# PROC091F_PMIC.net
KiCad netlist of a schematic drawn in Altium Designer
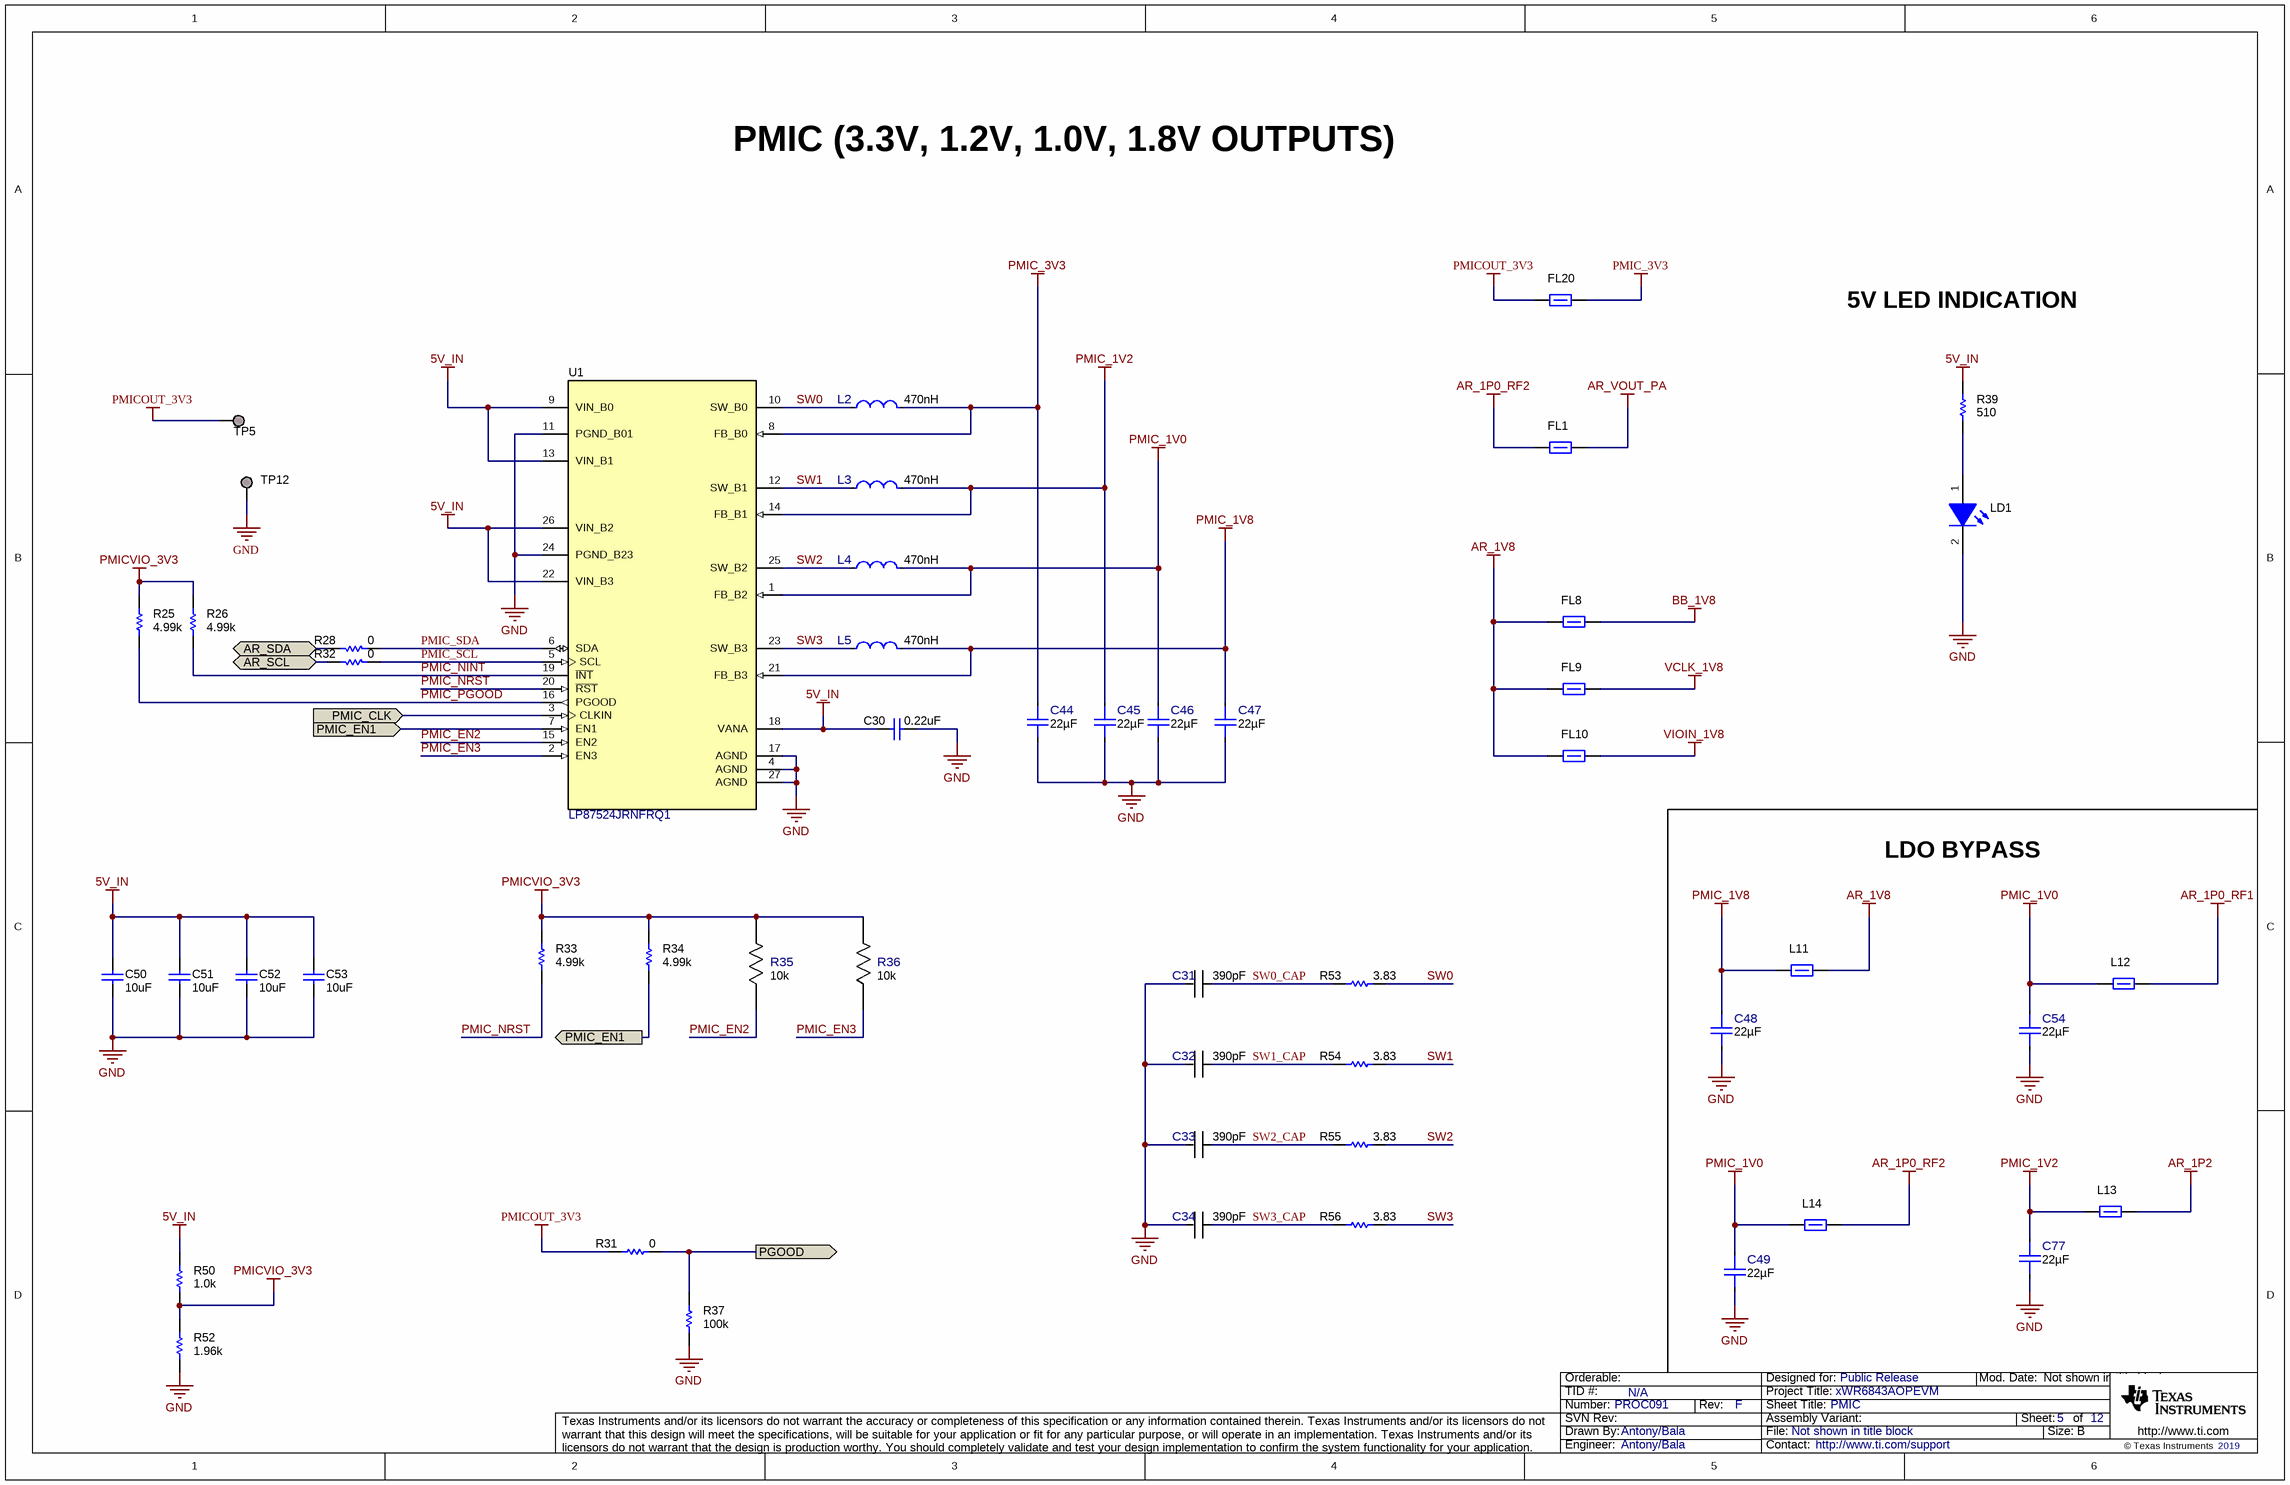
[diagram p0: PROC091F_PMIC.SchDoc]

(export (version "E")
  (design (tool "Eeschema 10.0.6"))
  (components
    (comp (ref "C30")
      (value "0.22uF")
      (footprint "0201_033L")
      (description "CAP, CERM, 0.22 uF, 10 V, +/- 20%, X5R, 0201")
      (fields
        (field (name "MANUFACTURER") "Taiyo Yuden")
        (field (name "PARTNUMBER") "LMK063BJ224MP-F")
        (field (name "PUBLISHER") "Texas Instruments")
      )
      (libsource (lib "Altium Vault - TI") (part "Capacitor"))
    )
    (comp (ref "C31")
      (value "TMK063CG391JT-F")
      (footprint "FP-TMK063CG391JT-F_0201 (0603 Metric)-IPC_C")
      (description "CAP CER 390PF 25V C0G/NP0 0201")
      (fields (field (name "CAP_F") "390pF") (field (name "MANUFACTURER") "Taiyo Yuden"))
      (libsource (lib "Altium Vault - TI") (part "SYM-B32642B0223J"))
    )
    (comp (ref "C32")
      (value "TMK063CG391JT-F")
      (footprint "FP-TMK063CG391JT-F_0201 (0603 Metric)-IPC_C")
      (description "CAP CER 390PF 25V C0G/NP0 0201")
      (fields (field (name "CAP_F") "390pF") (field (name "MANUFACTURER") "Taiyo Yuden"))
      (libsource (lib "Altium Vault - TI") (part "SYM-B32642B0223J"))
    )
    (comp (ref "C33")
      (value "TMK063CG391JT-F")
      (footprint "FP-TMK063CG391JT-F_0201 (0603 Metric)-IPC_C")
      (description "CAP CER 390PF 25V C0G/NP0 0201")
      (fields (field (name "CAP_F") "390pF") (field (name "MANUFACTURER") "Taiyo Yuden"))
      (libsource (lib "Altium Vault - TI") (part "SYM-B32642B0223J"))
    )
    (comp (ref "C34")
      (value "TMK063CG391JT-F")
      (footprint "FP-TMK063CG391JT-F_0201 (0603 Metric)-IPC_C")
      (description "CAP CER 390PF 25V C0G/NP0 0201")
      (fields (field (name "CAP_F") "390pF") (field (name "MANUFACTURER") "Taiyo Yuden"))
      (libsource (lib "Altium Vault - TI") (part "SYM-B32642B0223J"))
    )
    (comp (ref "C44")
      (value "CL05A226MQ5N6J8")
      (footprint "FP-CL05A226MQ5N6J8_0402-IPC_C")
      (description "CAP CER 22UF 6.3V X5R 0402")
      (fields (field (name "CAP_F") "22µF") (field (name "MANUFACTURER") "Samsung Electro-Mechanics"))
      (libsource (lib "Altium Vault - TI") (part "SYM-C0603C220K5RACAUTO"))
    )
    (comp (ref "C45")
      (value "CL05A226MQ5N6J8")
      (footprint "FP-CL05A226MQ5N6J8_0402-IPC_C")
      (description "CAP CER 22UF 6.3V X5R 0402")
      (fields (field (name "CAP_F") "22µF") (field (name "MANUFACTURER") "Samsung Electro-Mechanics"))
      (libsource (lib "Altium Vault - TI") (part "SYM-C0603C220K5RACAUTO"))
    )
    (comp (ref "C46")
      (value "CL05A226MQ5N6J8")
      (footprint "FP-CL05A226MQ5N6J8_0402-IPC_C")
      (description "CAP CER 22UF 6.3V X5R 0402")
      (fields (field (name "CAP_F") "22µF") (field (name "MANUFACTURER") "Samsung Electro-Mechanics"))
      (libsource (lib "Altium Vault - TI") (part "SYM-C0603C220K5RACAUTO"))
    )
    (comp (ref "C47")
      (value "CL05A226MQ5N6J8")
      (footprint "FP-CL05A226MQ5N6J8_0402-IPC_C")
      (description "CAP CER 22UF 6.3V X5R 0402")
      (fields (field (name "CAP_F") "22µF") (field (name "MANUFACTURER") "Samsung Electro-Mechanics"))
      (libsource (lib "Altium Vault - TI") (part "SYM-C0603C220K5RACAUTO"))
    )
    (comp (ref "C48")
      (value "CL05A226MQ5N6J8")
      (footprint "FP-CL05A226MQ5N6J8_0402-IPC_C")
      (description "CAP CER 22UF 6.3V X5R 0402")
      (fields (field (name "CAP_F") "22µF") (field (name "MANUFACTURER") "Samsung Electro-Mechanics"))
      (libsource (lib "Altium Vault - TI") (part "SYM-C0603C220K5RACAUTO"))
    )
    (comp (ref "C49")
      (value "CL05A226MQ5N6J8")
      (footprint "FP-CL05A226MQ5N6J8_0402-IPC_C")
      (description "CAP CER 22UF 6.3V X5R 0402")
      (fields (field (name "CAP_F") "22µF") (field (name "MANUFACTURER") "Samsung Electro-Mechanics"))
      (libsource (lib "Altium Vault - TI") (part "SYM-C0603C220K5RACAUTO"))
    )
    (comp (ref "C50")
      (value "10uF")
      (footprint "0402_070")
      (description "CAP, CERM, 10 uF, 10 V, +/- 20%, X5R, 0402")
      (fields
        (field (name "MANUFACTURER") "Samsung Electro-Mechanics")
        (field (name "PARTNUMBER") "CL05A106MP5NUNC")
      )
      (libsource (lib "Altium Vault - TI") (part "Capacitor"))
    )
    (comp (ref "C51")
      (value "10uF")
      (footprint "0402_070")
      (description "CAP, CERM, 10 uF, 10 V, +/- 20%, X5R, 0402")
      (fields
        (field (name "MANUFACTURER") "Samsung Electro-Mechanics")
        (field (name "PARTNUMBER") "CL05A106MP5NUNC")
      )
      (libsource (lib "Altium Vault - TI") (part "Capacitor"))
    )
    (comp (ref "C52")
      (value "10uF")
      (footprint "0402_070")
      (description "CAP, CERM, 10 uF, 10 V, +/- 20%, X5R, 0402")
      (fields
        (field (name "MANUFACTURER") "Samsung Electro-Mechanics")
        (field (name "PARTNUMBER") "CL05A106MP5NUNC")
      )
      (libsource (lib "Altium Vault - TI") (part "Capacitor"))
    )
    (comp (ref "C53")
      (value "10uF")
      (footprint "0402_070")
      (description "CAP, CERM, 10 uF, 10 V, +/- 20%, X5R, 0402")
      (fields
        (field (name "MANUFACTURER") "Samsung Electro-Mechanics")
        (field (name "PARTNUMBER") "CL05A106MP5NUNC")
      )
      (libsource (lib "Altium Vault - TI") (part "Capacitor"))
    )
    (comp (ref "C54")
      (value "CL05A226MQ5N6J8")
      (footprint "FP-CL05A226MQ5N6J8_0402-IPC_C")
      (description "CAP CER 22UF 6.3V X5R 0402")
      (fields (field (name "CAP_F") "22µF") (field (name "MANUFACTURER") "Samsung Electro-Mechanics"))
      (libsource (lib "Altium Vault - TI") (part "SYM-C0603C220K5RACAUTO"))
    )
    (comp (ref "C77")
      (value "CL05A226MQ5N6J8")
      (footprint "FP-CL05A226MQ5N6J8_0402-IPC_C")
      (description "CAP CER 22UF 6.3V X5R 0402")
      (fields (field (name "CAP_F") "22µF") (field (name "MANUFACTURER") "Samsung Electro-Mechanics"))
      (libsource (lib "Altium Vault - TI") (part "SYM-C0603C220K5RACAUTO"))
    )
    (comp (ref "FL1")
      (value "BLM15PD300SZ1D")
      (footprint "0402L")
      (description "Inductor, Ferrite Bead, Ferrite, 2.2 A, 0.035 ohm, AEC-Q200 Grade 1, SMD")
      (fields (field (name "MANUFACTURER") "MuRata") (field (name "PUBLISHER") "Texas Instruments"))
      (libsource (lib "Altium Vault - TI") (part "Ferrite_Bead"))
    )
    (comp (ref "FL8")
      (value "BLM15PD300SZ1D")
      (footprint "0402L")
      (description "Inductor, Ferrite Bead, Ferrite, 2.2 A, 0.035 ohm, AEC-Q200 Grade 1, SMD")
      (fields (field (name "MANUFACTURER") "MuRata") (field (name "PUBLISHER") "Texas Instruments"))
      (libsource (lib "Altium Vault - TI") (part "Ferrite_Bead"))
    )
    (comp (ref "FL9")
      (value "BLM15PD300SZ1D")
      (footprint "0402L")
      (description "Inductor, Ferrite Bead, Ferrite, 2.2 A, 0.035 ohm, AEC-Q200 Grade 1, SMD")
      (fields (field (name "MANUFACTURER") "MuRata") (field (name "PUBLISHER") "Texas Instruments"))
      (libsource (lib "Altium Vault - TI") (part "Ferrite_Bead"))
    )
    (comp (ref "FL10")
      (value "BLM15PD300SZ1D")
      (footprint "0402L")
      (description "Inductor, Ferrite Bead, Ferrite, 2.2 A, 0.035 ohm, AEC-Q200 Grade 1, SMD")
      (fields (field (name "MANUFACTURER") "MuRata") (field (name "PUBLISHER") "Texas Instruments"))
      (libsource (lib "Altium Vault - TI") (part "Ferrite_Bead"))
    )
    (comp (ref "FL20")
      (value "BLM15PD300SZ1D")
      (footprint "0402L")
      (description "Inductor, Ferrite Bead, Ferrite, 2.2 A, 0.035 ohm, AEC-Q200 Grade 1, SMD")
      (fields (field (name "MANUFACTURER") "MuRata") (field (name "PUBLISHER") "Texas Instruments"))
      (libsource (lib "Altium Vault - TI") (part "Ferrite_Bead"))
    )
    (comp (ref "L2")
      (value "MCKK2012TR47M")
      (footprint "FP-MCKK2012TR47M_0805 (2012 Metric)-IPC_C")
      (description "FIXED IND 470NH 4.5A 39 MOHM SMD")
      (fields (field (name "IND_H") "470nH") (field (name "MANUFACTURER") "Taiyo Yuden"))
      (libsource (lib "Altium Vault - TI") (part "SYM-XEL3530-681MEC"))
    )
    (comp (ref "L3")
      (value "MCKK2012TR47M")
      (footprint "FP-MCKK2012TR47M_0805 (2012 Metric)-IPC_C")
      (description "FIXED IND 470NH 4.5A 39 MOHM SMD")
      (fields (field (name "IND_H") "470nH") (field (name "MANUFACTURER") "Taiyo Yuden"))
      (libsource (lib "Altium Vault - TI") (part "SYM-XEL3530-681MEC"))
    )
    (comp (ref "L4")
      (value "MCKK2012TR47M")
      (footprint "FP-MCKK2012TR47M_0805 (2012 Metric)-IPC_C")
      (description "FIXED IND 470NH 4.5A 39 MOHM SMD")
      (fields (field (name "IND_H") "470nH") (field (name "MANUFACTURER") "Taiyo Yuden"))
      (libsource (lib "Altium Vault - TI") (part "SYM-XEL3530-681MEC"))
    )
    (comp (ref "L5")
      (value "MCKK2012TR47M")
      (footprint "FP-MCKK2012TR47M_0805 (2012 Metric)-IPC_C")
      (description "FIXED IND 470NH 4.5A 39 MOHM SMD")
      (fields (field (name "IND_H") "470nH") (field (name "MANUFACTURER") "Taiyo Yuden"))
      (libsource (lib "Altium Vault - TI") (part "SYM-XEL3530-681MEC"))
    )
    (comp (ref "L11")
      (value "BLM18SG260TN1D")
      (footprint "0603L")
      (description "Ferrite Bead, 26 ohm @ 100 MHz, 6 A, 0603")
      (fields (field (name "MANUFACTURER") "MuRata") (field (name "PUBLISHER") "Texas Instruments"))
      (libsource (lib "Altium Vault - TI") (part "Ferrite_Bead"))
    )
    (comp (ref "L12")
      (value "BLM18SG260TN1D")
      (footprint "0603L")
      (description "Ferrite Bead, 26 ohm @ 100 MHz, 6 A, 0603")
      (fields (field (name "MANUFACTURER") "MuRata") (field (name "PUBLISHER") "Texas Instruments"))
      (libsource (lib "Altium Vault - TI") (part "Ferrite_Bead"))
    )
    (comp (ref "L13")
      (value "BLM18SG260TN1D")
      (footprint "0603L")
      (description "Ferrite Bead, 26 ohm @ 100 MHz, 6 A, 0603")
      (fields (field (name "MANUFACTURER") "MuRata") (field (name "PUBLISHER") "Texas Instruments"))
      (libsource (lib "Altium Vault - TI") (part "Ferrite_Bead"))
    )
    (comp (ref "L14")
      (value "BLM18SG260TN1D")
      (footprint "0603L")
      (description "Ferrite Bead, 26 ohm @ 100 MHz, 6 A, 0603")
      (fields (field (name "MANUFACTURER") "MuRata") (field (name "PUBLISHER") "Texas Instruments"))
      (libsource (lib "Altium Vault - TI") (part "Ferrite_Bead"))
    )
    (comp (ref "LD1")
      (value "APHHS1005CGCK")
      (footprint "APHHS1005_Green")
      (description "LED, Green, SMD")
      (fields (field (name "MANUFACTURER") "Kingbright"))
      (libsource (lib "Altium Vault - TI") (part "LED"))
    )
    (comp (ref "R25")
      (value "4.99k")
      (footprint "0201L")
      (description "RES, 4.99 k, 1%, 0.05 W, 0201")
      (fields
        (field (name "MANUFACTURER") "Yageo America")
        (field (name "PARTNUMBER") "RC0201FR-074K99L")
        (field (name "PUBLISHER") "Texas Instruments")
      )
      (libsource (lib "Altium Vault - TI") (part "Resistor"))
    )
    (comp (ref "R26")
      (value "4.99k")
      (footprint "0201L")
      (description "RES, 4.99 k, 1%, 0.05 W, 0201")
      (fields
        (field (name "MANUFACTURER") "Yageo America")
        (field (name "PARTNUMBER") "RC0201FR-074K99L")
        (field (name "PUBLISHER") "Texas Instruments")
      )
      (libsource (lib "Altium Vault - TI") (part "Resistor"))
    )
    (comp (ref "R28")
      (value "RC0201JR-070RL")
      (footprint "FP-RC0201JR-070RL_0201 (0603 Metric)-MFG")
      (description "RES SMD 0 OHM JUMPER 1/20W 0201")
      (fields (field (name "MANUFACTURER") "Yageo") (field (name "RES_OHM") "0"))
      (libsource (lib "Altium Vault - TI") (part "SYM-WSR3R1500F"))
    )
    (comp (ref "R31")
      (value "RC0201JR-070RL")
      (footprint "FP-RC0201JR-070RL_0201 (0603 Metric)-MFG")
      (description "RES SMD 0 OHM JUMPER 1/20W 0201")
      (fields (field (name "MANUFACTURER") "Yageo") (field (name "RES_OHM") "0"))
      (libsource (lib "Altium Vault - TI") (part "SYM-WSR3R1500F"))
    )
    (comp (ref "R32")
      (value "RC0201JR-070RL")
      (footprint "FP-RC0201JR-070RL_0201 (0603 Metric)-MFG")
      (description "RES SMD 0 OHM JUMPER 1/20W 0201")
      (fields (field (name "MANUFACTURER") "Yageo") (field (name "RES_OHM") "0"))
      (libsource (lib "Altium Vault - TI") (part "SYM-WSR3R1500F"))
    )
    (comp (ref "R33")
      (value "4.99k")
      (footprint "0201L")
      (description "RES, 4.99 k, 1%, 0.05 W, 0201")
      (fields
        (field (name "MANUFACTURER") "Yageo America")
        (field (name "PARTNUMBER") "RC0201FR-074K99L")
        (field (name "PUBLISHER") "Texas Instruments")
      )
      (libsource (lib "Altium Vault - TI") (part "Resistor"))
    )
    (comp (ref "R34")
      (value "4.99k")
      (footprint "0201L")
      (description "RES, 4.99 k, 1%, 0.05 W, 0201")
      (fields
        (field (name "MANUFACTURER") "Yageo America")
        (field (name "PARTNUMBER") "RC0201FR-074K99L")
        (field (name "PUBLISHER") "Texas Instruments")
      )
      (libsource (lib "Altium Vault - TI") (part "Resistor"))
    )
    (comp (ref "R35")
      (value "RR0306P-103-D")
      (footprint "FP-RR0306P-103-D_0201-IPC_C")
      (description "10 kOhms ±0.5% 0.05W, 1/20W Chip Resistor 0201 (0603 Metric)  Thin Film")
      (fields (field (name "MANUFACTURER") "Susumu") (field (name "RES_OHM") "10k"))
      (libsource (lib "Altium Vault - TI") (part "SYM-PMR18EZPJ000"))
    )
    (comp (ref "R36")
      (value "RR0306P-103-D")
      (footprint "FP-RR0306P-103-D_0201-IPC_C")
      (description "10 kOhms ±0.5% 0.05W, 1/20W Chip Resistor 0201 (0603 Metric)  Thin Film")
      (fields (field (name "MANUFACTURER") "Susumu") (field (name "RES_OHM") "10k"))
      (libsource (lib "Altium Vault - TI") (part "SYM-PMR18EZPJ000"))
    )
    (comp (ref "R37")
      (value "100k")
      (footprint "0201L")
      (description "RES, 100 k, 1%, 0.05 W, 0201")
      (fields (field (name "MANUFACTURER") "Vishay-Dale") (field (name "PARTNUMBER") "CRCW0201100KFKED"))
      (libsource (lib "Altium Vault - TI") (part "Resistor"))
    )
    (comp (ref "R39")
      (value "510")
      (footprint "0201L")
      (description "RES, 510, 5%, 0.05 W, 0201")
      (fields
        (field (name "MANUFACTURER") "Yageo America")
        (field (name "PARTNUMBER") "RC0201JR-07510RL")
        (field (name "PUBLISHER") "Texas Instruments")
      )
      (libsource (lib "Altium Vault - TI") (part "Resistor"))
    )
    (comp (ref "R50")
      (value "1.0k")
      (footprint "0201L")
      (description "RES, 1.0 k, 5%, 0.05 W, 0201")
      (fields
        (field (name "MANUFACTURER") "Yageo America")
        (field (name "PARTNUMBER") "RC0201JR-071KL")
        (field (name "PUBLISHER") "Texas Instruments")
      )
      (libsource (lib "Altium Vault - TI") (part "Resistor"))
    )
    (comp (ref "R52")
      (value "1.96k")
      (footprint "0201L")
      (description "RES, 1.96 k, 1%, 0.05 W, 0201")
      (fields
        (field (name "MANUFACTURER") "Yageo America")
        (field (name "PARTNUMBER") "RC0201FR-071K96L")
        (field (name "PUBLISHER") "Texas Instruments")
      )
      (libsource (lib "Altium Vault - TI") (part "Resistor"))
    )
    (comp (ref "R53")
      (value "RC0402FR-073R83L")
      (footprint "FP-RC0402FR-073R83L_0402 (1005 Metric)-IPC_C")
      (description "RES Thick Film SMD 3.83Ω 1% 1/16W 0402 200ppm/°C")
      (fields (field (name "RES_OHM") "3.83") (field (name "MANUFACTURER") "Yageo"))
      (libsource (lib "Altium Vault - TI") (part "SYM-WSR3R1500F"))
    )
    (comp (ref "R54")
      (value "RC0402FR-073R83L")
      (footprint "FP-RC0402FR-073R83L_0402 (1005 Metric)-IPC_C")
      (description "RES Thick Film SMD 3.83Ω 1% 1/16W 0402 200ppm/°C")
      (fields (field (name "RES_OHM") "3.83") (field (name "MANUFACTURER") "Yageo"))
      (libsource (lib "Altium Vault - TI") (part "SYM-WSR3R1500F"))
    )
    (comp (ref "R55")
      (value "RC0402FR-073R83L")
      (footprint "FP-RC0402FR-073R83L_0402 (1005 Metric)-IPC_C")
      (description "RES Thick Film SMD 3.83Ω 1% 1/16W 0402 200ppm/°C")
      (fields (field (name "RES_OHM") "3.83") (field (name "MANUFACTURER") "Yageo"))
      (libsource (lib "Altium Vault - TI") (part "SYM-WSR3R1500F"))
    )
    (comp (ref "R56")
      (value "RC0402FR-073R83L")
      (footprint "FP-RC0402FR-073R83L_0402 (1005 Metric)-IPC_C")
      (description "RES Thick Film SMD 3.83Ω 1% 1/16W 0402 200ppm/°C")
      (fields (field (name "RES_OHM") "3.83") (field (name "MANUFACTURER") "Yageo"))
      (libsource (lib "Altium Vault - TI") (part "SYM-WSR3R1500F"))
    )
    (comp (ref "TP5")
      (value "TESTPOINT")
      (footprint "TP_25MIL-SMT")
      (description "TEST POINT.  No entry in BOM.")
      (libsource (lib "Altium Vault - TI") (part "TESTPOINT"))
    )
    (comp (ref "TP12")
      (value "TESTPOINT")
      (footprint "TP_VIA_060RND040")
      (description "TEST POINT.  No entry in BOM.")
      (libsource (lib "Altium Vault - TI") (part "TESTPOINT"))
    )
    (comp (ref "U1")
      (value "LP87524JRNFRQ1")
      (footprint "RNF0026C")
      (description "4-A + 2.5-A + Two 1.5-A Buck Converters With Integrated Switches, RNF0026C (VQFN-HR-26)")
      (fields
        (field (name "ALTERNATE PARTNUMBER") "LP87524JRNFTQ1")
        (field (name "MANUFACTURER") "Texas Instruments")
      )
      (libsource (lib "Altium Vault - TI") (part "LP87524"))
    )
  )
  (nets
    (net (code "1") (name "/AR_SCL") (class "Default")
      (node (ref "R32") (pin "1") (pinfunction "1_1") (pintype "passive"))
    )
    (net (code "2") (name "/AR_SDA") (class "Default")
      (node (ref "R28") (pin "1") (pinfunction "1_1") (pintype "passive"))
    )
    (net (code "3") (name "/PGOOD") (class "Default")
      (node (ref "R31") (pin "1") (pinfunction "1_1") (pintype "passive"))
      (node (ref "R37") (pin "2") (pinfunction "2_2") (pintype "passive"))
    )
    (net (code "4") (name "/PMIC_CLK") (class "Default")
      (node (ref "U1") (pin "3") (pinfunction "CLKIN_3") (pintype "input"))
    )
    (net (code "5") (name "/PMIC_EN1") (class "Default")
      (node (ref "R34") (pin "1") (pinfunction "1_1") (pintype "passive"))
      (node (ref "U1") (pin "7") (pinfunction "EN1_7") (pintype "input"))
    )
    (net (code "6") (name "/PMIC_EN2") (class "Default")
      (node (ref "R35") (pin "1") (pinfunction "1_1") (pintype "passive"))
      (node (ref "U1") (pin "15") (pinfunction "EN2_15") (pintype "input"))
    )
    (net (code "7") (name "/PMIC_EN3") (class "Default")
      (node (ref "R36") (pin "1") (pinfunction "1_1") (pintype "passive"))
      (node (ref "U1") (pin "2") (pinfunction "EN3_2") (pintype "input"))
    )
    (net (code "8") (name "/PMIC_NINT") (class "Default")
      (node (ref "R26") (pin "1") (pinfunction "1_1") (pintype "passive"))
      (node (ref "U1") (pin "19") (pinfunction "INT_19") (pintype "open_collector"))
    )
    (net (code "9") (name "/PMIC_NRST") (class "Default")
      (node (ref "R33") (pin "1") (pinfunction "1_1") (pintype "passive"))
      (node (ref "U1") (pin "20") (pinfunction "RST_20") (pintype "input"))
    )
    (net (code "10") (name "/PMIC_PGOOD") (class "Default")
      (node (ref "R25") (pin "1") (pinfunction "1_1") (pintype "passive"))
      (node (ref "U1") (pin "16") (pinfunction "PGOOD_16") (pintype "output"))
    )
    (net (code "11") (name "/PMIC_SCL") (class "Default")
      (node (ref "R32") (pin "2") (pinfunction "2_2") (pintype "passive"))
      (node (ref "U1") (pin "5") (pinfunction "SCL_5") (pintype "input"))
    )
    (net (code "12") (name "/PMIC_SDA") (class "Default")
      (node (ref "R28") (pin "2") (pinfunction "2_2") (pintype "passive"))
      (node (ref "U1") (pin "6") (pinfunction "SDA_6") (pintype "bidirectional"))
    )
    (net (code "13") (name "/SW0") (class "Default")
      (node (ref "L2") (pin "2") (pinfunction "2_2") (pintype "passive"))
      (node (ref "R53") (pin "2") (pinfunction "2_2") (pintype "passive"))
      (node (ref "U1") (pin "10") (pinfunction "SW_B0_10") (pintype "power_in"))
    )
    (net (code "14") (name "/SW0_CAP") (class "Default")
      (node (ref "C31") (pin "1") (pinfunction "1_1") (pintype "passive"))
      (node (ref "R53") (pin "1") (pinfunction "1_1") (pintype "passive"))
    )
    (net (code "15") (name "/SW1") (class "Default")
      (node (ref "L3") (pin "2") (pinfunction "2_2") (pintype "passive"))
      (node (ref "R54") (pin "2") (pinfunction "2_2") (pintype "passive"))
      (node (ref "U1") (pin "12") (pinfunction "SW_B1_12") (pintype "power_in"))
    )
    (net (code "16") (name "/SW1_CAP") (class "Default")
      (node (ref "C32") (pin "1") (pinfunction "1_1") (pintype "passive"))
      (node (ref "R54") (pin "1") (pinfunction "1_1") (pintype "passive"))
    )
    (net (code "17") (name "/SW2") (class "Default")
      (node (ref "L4") (pin "2") (pinfunction "2_2") (pintype "passive"))
      (node (ref "R55") (pin "2") (pinfunction "2_2") (pintype "passive"))
      (node (ref "U1") (pin "25") (pinfunction "SW_B2_25") (pintype "power_in"))
    )
    (net (code "18") (name "/SW2_CAP") (class "Default")
      (node (ref "C33") (pin "1") (pinfunction "1_1") (pintype "passive"))
      (node (ref "R55") (pin "1") (pinfunction "1_1") (pintype "passive"))
    )
    (net (code "19") (name "/SW3") (class "Default")
      (node (ref "L5") (pin "2") (pinfunction "2_2") (pintype "passive"))
      (node (ref "R56") (pin "2") (pinfunction "2_2") (pintype "passive"))
      (node (ref "U1") (pin "23") (pinfunction "SW_B3_23") (pintype "power_in"))
    )
    (net (code "20") (name "/SW3_CAP") (class "Default")
      (node (ref "C34") (pin "1") (pinfunction "1_1") (pintype "passive"))
      (node (ref "R56") (pin "1") (pinfunction "1_1") (pintype "passive"))
    )
    (net (code "21") (name "5V_IN") (class "Default")
      (node (ref "C30") (pin "1") (pinfunction "1_1") (pintype "passive"))
      (node (ref "C50") (pin "1") (pinfunction "1_1") (pintype "passive"))
      (node (ref "C51") (pin "1") (pinfunction "1_1") (pintype "passive"))
      (node (ref "C52") (pin "1") (pinfunction "1_1") (pintype "passive"))
      (node (ref "C53") (pin "1") (pinfunction "1_1") (pintype "passive"))
      (node (ref "R39") (pin "1") (pinfunction "1_1") (pintype "passive"))
      (node (ref "R50") (pin "2") (pinfunction "2_2") (pintype "passive"))
      (node (ref "U1") (pin "13") (pinfunction "VIN_B1_13") (pintype "power_in"))
      (node (ref "U1") (pin "18") (pinfunction "VANA_18") (pintype "power_in"))
      (node (ref "U1") (pin "22") (pinfunction "VIN_B3_22") (pintype "power_in"))
      (node (ref "U1") (pin "26") (pinfunction "VIN_B2_26") (pintype "power_in"))
      (node (ref "U1") (pin "9") (pinfunction "VIN_B0_9") (pintype "power_in"))
    )
    (net (code "22") (name "AR_1P0_RF1") (class "Default")
      (node (ref "L12") (pin "2") (pinfunction "2_2") (pintype "passive"))
    )
    (net (code "23") (name "AR_1P0_RF2") (class "Default")
      (node (ref "FL1") (pin "1") (pinfunction "1_1") (pintype "passive"))
      (node (ref "L14") (pin "2") (pinfunction "2_2") (pintype "passive"))
    )
    (net (code "24") (name "AR_1P2") (class "Default")
      (node (ref "L13") (pin "2") (pinfunction "2_2") (pintype "passive"))
    )
    (net (code "25") (name "AR_1V8") (class "Default")
      (node (ref "FL10") (pin "1") (pinfunction "1_1") (pintype "passive"))
      (node (ref "FL8") (pin "1") (pinfunction "1_1") (pintype "passive"))
      (node (ref "FL9") (pin "1") (pinfunction "1_1") (pintype "passive"))
      (node (ref "L11") (pin "2") (pinfunction "2_2") (pintype "passive"))
    )
    (net (code "26") (name "AR_VOUT_PA") (class "Default")
      (node (ref "FL1") (pin "2") (pinfunction "2_2") (pintype "passive"))
    )
    (net (code "27") (name "BB_1V8") (class "Default")
      (node (ref "FL8") (pin "2") (pinfunction "2_2") (pintype "passive"))
    )
    (net (code "28") (name "GND") (class "Default")
      (node (ref "C30") (pin "2") (pinfunction "2_2") (pintype "passive"))
      (node (ref "C31") (pin "2") (pinfunction "2_2") (pintype "passive"))
      (node (ref "C32") (pin "2") (pinfunction "2_2") (pintype "passive"))
      (node (ref "C33") (pin "2") (pinfunction "2_2") (pintype "passive"))
      (node (ref "C34") (pin "2") (pinfunction "2_2") (pintype "passive"))
      (node (ref "C44") (pin "2") (pinfunction "2_2") (pintype "passive"))
      (node (ref "C45") (pin "2") (pinfunction "2_2") (pintype "passive"))
      (node (ref "C46") (pin "2") (pinfunction "2_2") (pintype "passive"))
      (node (ref "C47") (pin "2") (pinfunction "2_2") (pintype "passive"))
      (node (ref "C48") (pin "2") (pinfunction "2_2") (pintype "passive"))
      (node (ref "C49") (pin "2") (pinfunction "2_2") (pintype "passive"))
      (node (ref "C50") (pin "2") (pinfunction "2_2") (pintype "passive"))
      (node (ref "C51") (pin "2") (pinfunction "2_2") (pintype "passive"))
      (node (ref "C52") (pin "2") (pinfunction "2_2") (pintype "passive"))
      (node (ref "C53") (pin "2") (pinfunction "2_2") (pintype "passive"))
      (node (ref "C54") (pin "2") (pinfunction "2_2") (pintype "passive"))
      (node (ref "C77") (pin "2") (pinfunction "2_2") (pintype "passive"))
      (node (ref "LD1") (pin "2") (pinfunction "K_2") (pintype "passive"))
      (node (ref "R37") (pin "1") (pinfunction "1_1") (pintype "passive"))
      (node (ref "R52") (pin "1") (pinfunction "1_1") (pintype "passive"))
      (node (ref "TP12") (pin "1") (pintype "passive"))
      (node (ref "U1") (pin "11") (pinfunction "PGND_B01_11") (pintype "power_in"))
      (node (ref "U1") (pin "17") (pinfunction "AGND_17") (pintype "power_in"))
      (node (ref "U1") (pin "24") (pinfunction "PGND_B23_24") (pintype "power_in"))
      (node (ref "U1") (pin "27") (pinfunction "AGND_27") (pintype "power_in"))
      (node (ref "U1") (pin "4") (pinfunction "AGND_4") (pintype "power_in"))
    )
    (net (code "29") (name "Net-(LD1-A)") (class "Default")
      (node (ref "LD1") (pin "1") (pinfunction "A_1") (pintype "passive"))
      (node (ref "R39") (pin "2") (pinfunction "2_2") (pintype "passive"))
    )
    (net (code "30") (name "PMICOUT_3V3") (class "Default")
      (node (ref "FL20") (pin "1") (pinfunction "1_1") (pintype "passive"))
      (node (ref "R31") (pin "2") (pinfunction "2_2") (pintype "passive"))
      (node (ref "TP5") (pin "1") (pintype "passive"))
    )
    (net (code "31") (name "PMICVIO_3V3") (class "Default")
      (node (ref "R25") (pin "2") (pinfunction "2_2") (pintype "passive"))
      (node (ref "R26") (pin "2") (pinfunction "2_2") (pintype "passive"))
      (node (ref "R33") (pin "2") (pinfunction "2_2") (pintype "passive"))
      (node (ref "R34") (pin "2") (pinfunction "2_2") (pintype "passive"))
      (node (ref "R35") (pin "2") (pinfunction "2_2") (pintype "passive"))
      (node (ref "R36") (pin "2") (pinfunction "2_2") (pintype "passive"))
      (node (ref "R50") (pin "1") (pinfunction "1_1") (pintype "passive"))
      (node (ref "R52") (pin "2") (pinfunction "2_2") (pintype "passive"))
    )
    (net (code "32") (name "PMIC_1V0") (class "Default")
      (node (ref "C46") (pin "1") (pinfunction "1_1") (pintype "passive"))
      (node (ref "C49") (pin "1") (pinfunction "1_1") (pintype "passive"))
      (node (ref "C54") (pin "1") (pinfunction "1_1") (pintype "passive"))
      (node (ref "L12") (pin "1") (pinfunction "1_1") (pintype "passive"))
      (node (ref "L14") (pin "1") (pinfunction "1_1") (pintype "passive"))
      (node (ref "L4") (pin "1") (pinfunction "1_1") (pintype "passive"))
      (node (ref "U1") (pin "1") (pinfunction "FB_B2_1") (pintype "input"))
    )
    (net (code "33") (name "PMIC_1V2") (class "Default")
      (node (ref "C45") (pin "1") (pinfunction "1_1") (pintype "passive"))
      (node (ref "C77") (pin "1") (pinfunction "1_1") (pintype "passive"))
      (node (ref "L13") (pin "1") (pinfunction "1_1") (pintype "passive"))
      (node (ref "L3") (pin "1") (pinfunction "1_1") (pintype "passive"))
      (node (ref "U1") (pin "14") (pinfunction "FB_B1_14") (pintype "input"))
    )
    (net (code "34") (name "PMIC_1V8") (class "Default")
      (node (ref "C47") (pin "1") (pinfunction "1_1") (pintype "passive"))
      (node (ref "C48") (pin "1") (pinfunction "1_1") (pintype "passive"))
      (node (ref "L11") (pin "1") (pinfunction "1_1") (pintype "passive"))
      (node (ref "L5") (pin "1") (pinfunction "1_1") (pintype "passive"))
      (node (ref "U1") (pin "21") (pinfunction "FB_B3_21") (pintype "input"))
    )
    (net (code "35") (name "PMIC_3V3") (class "Default")
      (node (ref "C44") (pin "1") (pinfunction "1_1") (pintype "passive"))
      (node (ref "FL20") (pin "2") (pinfunction "2_2") (pintype "passive"))
      (node (ref "L2") (pin "1") (pinfunction "1_1") (pintype "passive"))
      (node (ref "U1") (pin "8") (pinfunction "FB_B0_8") (pintype "input"))
    )
    (net (code "36") (name "VCLK_1V8") (class "Default")
      (node (ref "FL9") (pin "2") (pinfunction "2_2") (pintype "passive"))
    )
    (net (code "37") (name "VIOIN_1V8") (class "Default")
      (node (ref "FL10") (pin "2") (pinfunction "2_2") (pintype "passive"))
    )
  )
)
